# 21_GPIOs_EXP.net
KiCad netlist of a schematic drawn in Altium Designer
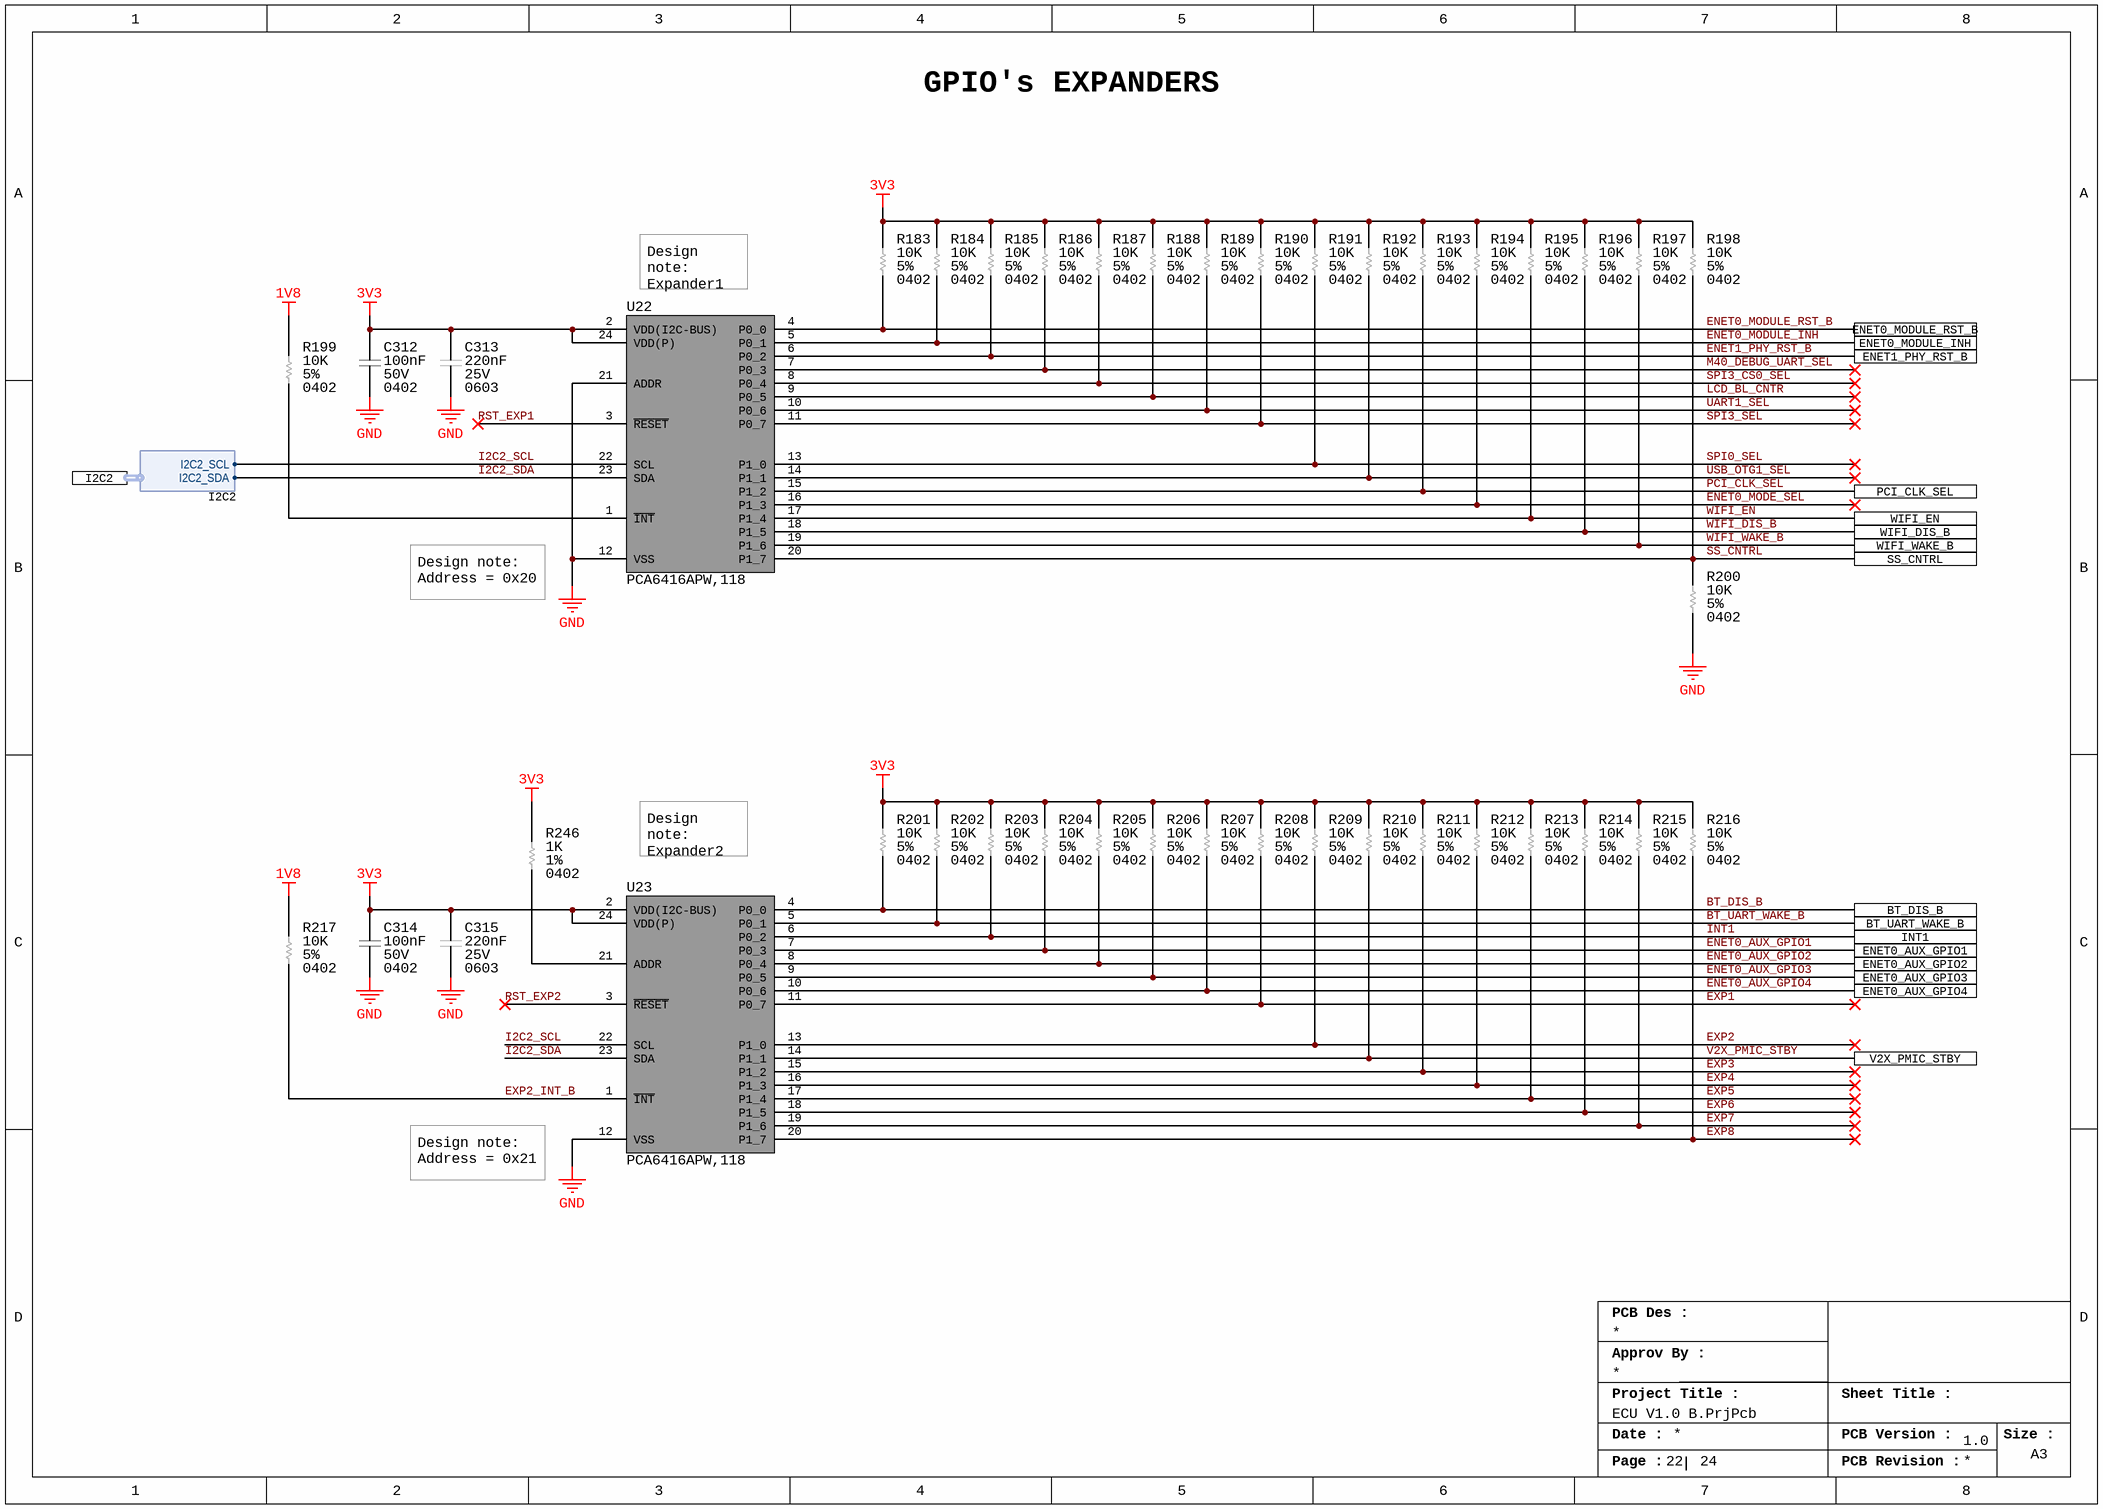
[diagram p0: 21_GPIOs_EXP.SchDoc]

(export (version "E")
  (design (tool "Eeschema 10.0.6"))
  (components
    (comp (ref "C312")
      (value "GRM155R71H104KE14D")
      (footprint "CAP_0402_CAPC1005X05N")
      (description "Multilayer Ceramic Capacitor, 0.1 uF, 16 V, ± 10%, X7R, 0402 [1005 Metric]")
      (fields
        (field (name "MANUFACTURER") "Murata")
        (field (name "TOLERANCE") "10%")
        (field (name "VOLTAGE RATING") "50V")
        (field (name "CAPACITANCE") "100nF")
        (field (name "CASE/PACKAGE") "0402")
      )
      (libsource (lib "Electronic Devices_LIB") (part "CAP_100NF_50V_X7R_0402"))
    )
    (comp (ref "C313")
      (value "GRM188R71E224KA88D")
      (footprint "CAP_0603_CAPC1608X08N")
      (description "Multilayer Ceramic Capacitor, 0.22 uF, 25 V, ± 10%, X7R, 0603 [1608 Metric]")
      (fields
        (field (name "MANUFACTURER") "Murata")
        (field (name "TOLERANCE") "10%")
        (field (name "CASE/PACKAGE") "0603")
        (field (name "VOLTAGE RATING") "25V")
        (field (name "CAPACITANCE") "220nF")
      )
      (libsource (lib "Electronic Devices_LIB") (part "CAP_0.22uF_25V_X7R_0603"))
    )
    (comp (ref "C314")
      (value "GRM155R71H104KE14D")
      (footprint "CAP_0402_CAPC1005X05N")
      (description "Multilayer Ceramic Capacitor, 0.1 uF, 16 V, ± 10%, X7R, 0402 [1005 Metric]")
      (fields
        (field (name "MANUFACTURER") "Murata")
        (field (name "TOLERANCE") "10%")
        (field (name "VOLTAGE RATING") "50V")
        (field (name "CAPACITANCE") "100nF")
        (field (name "CASE/PACKAGE") "0402")
      )
      (libsource (lib "Electronic Devices_LIB") (part "CAP_100NF_50V_X7R_0402"))
    )
    (comp (ref "C315")
      (value "GRM188R71E224KA88D")
      (footprint "CAP_0603_CAPC1608X08N")
      (description "Multilayer Ceramic Capacitor, 0.22 uF, 25 V, ± 10%, X7R, 0603 [1608 Metric]")
      (fields
        (field (name "MANUFACTURER") "Murata")
        (field (name "TOLERANCE") "10%")
        (field (name "CASE/PACKAGE") "0603")
        (field (name "VOLTAGE RATING") "25V")
        (field (name "CAPACITANCE") "220nF")
      )
      (libsource (lib "Electronic Devices_LIB") (part "CAP_0.22uF_25V_X7R_0603"))
    )
    (comp (ref "R183")
      (value "ERJ-2GEJ103X")
      (footprint "RES_0402_RESC1005X04N")
      (description "Res Thick Film 0402 10K Ohm 5% 1/10W ±200ppm/°C Molded SMD Punched Carrier T/R")
      (fields
        (field (name "MANUFACTURER") "Panasonic")
        (field (name "TOLERANCE") "5%")
        (field (name "RESISTANCE") "10K")
        (field (name "CASE/PACKAGE") "0402")
      )
      (libsource (lib "Electronic Devices_LIB") (part "RES_10K_5%_100mW_0402"))
    )
    (comp (ref "R184")
      (value "ERJ-2GEJ103X")
      (footprint "RES_0402_RESC1005X04N")
      (description "Res Thick Film 0402 10K Ohm 5% 1/10W ±200ppm/°C Molded SMD Punched Carrier T/R")
      (fields
        (field (name "MANUFACTURER") "Panasonic")
        (field (name "TOLERANCE") "5%")
        (field (name "RESISTANCE") "10K")
        (field (name "CASE/PACKAGE") "0402")
      )
      (libsource (lib "Electronic Devices_LIB") (part "RES_10K_5%_100mW_0402"))
    )
    (comp (ref "R185")
      (value "ERJ-2GEJ103X")
      (footprint "RES_0402_RESC1005X04N")
      (description "Res Thick Film 0402 10K Ohm 5% 1/10W ±200ppm/°C Molded SMD Punched Carrier T/R")
      (fields
        (field (name "MANUFACTURER") "Panasonic")
        (field (name "TOLERANCE") "5%")
        (field (name "RESISTANCE") "10K")
        (field (name "CASE/PACKAGE") "0402")
      )
      (libsource (lib "Electronic Devices_LIB") (part "RES_10K_5%_100mW_0402"))
    )
    (comp (ref "R186")
      (value "ERJ-2GEJ103X")
      (footprint "RES_0402_RESC1005X04N")
      (description "Res Thick Film 0402 10K Ohm 5% 1/10W ±200ppm/°C Molded SMD Punched Carrier T/R")
      (fields
        (field (name "MANUFACTURER") "Panasonic")
        (field (name "TOLERANCE") "5%")
        (field (name "RESISTANCE") "10K")
        (field (name "CASE/PACKAGE") "0402")
      )
      (libsource (lib "Electronic Devices_LIB") (part "RES_10K_5%_100mW_0402"))
    )
    (comp (ref "R187")
      (value "ERJ-2GEJ103X")
      (footprint "RES_0402_RESC1005X04N")
      (description "Res Thick Film 0402 10K Ohm 5% 1/10W ±200ppm/°C Molded SMD Punched Carrier T/R")
      (fields
        (field (name "MANUFACTURER") "Panasonic")
        (field (name "TOLERANCE") "5%")
        (field (name "RESISTANCE") "10K")
        (field (name "CASE/PACKAGE") "0402")
      )
      (libsource (lib "Electronic Devices_LIB") (part "RES_10K_5%_100mW_0402"))
    )
    (comp (ref "R188")
      (value "ERJ-2GEJ103X")
      (footprint "RES_0402_RESC1005X04N")
      (description "Res Thick Film 0402 10K Ohm 5% 1/10W ±200ppm/°C Molded SMD Punched Carrier T/R")
      (fields
        (field (name "MANUFACTURER") "Panasonic")
        (field (name "TOLERANCE") "5%")
        (field (name "RESISTANCE") "10K")
        (field (name "CASE/PACKAGE") "0402")
      )
      (libsource (lib "Electronic Devices_LIB") (part "RES_10K_5%_100mW_0402"))
    )
    (comp (ref "R189")
      (value "ERJ-2GEJ103X")
      (footprint "RES_0402_RESC1005X04N")
      (description "Res Thick Film 0402 10K Ohm 5% 1/10W ±200ppm/°C Molded SMD Punched Carrier T/R")
      (fields
        (field (name "MANUFACTURER") "Panasonic")
        (field (name "TOLERANCE") "5%")
        (field (name "RESISTANCE") "10K")
        (field (name "CASE/PACKAGE") "0402")
      )
      (libsource (lib "Electronic Devices_LIB") (part "RES_10K_5%_100mW_0402"))
    )
    (comp (ref "R190")
      (value "ERJ-2GEJ103X")
      (footprint "RES_0402_RESC1005X04N")
      (description "Res Thick Film 0402 10K Ohm 5% 1/10W ±200ppm/°C Molded SMD Punched Carrier T/R")
      (fields
        (field (name "MANUFACTURER") "Panasonic")
        (field (name "TOLERANCE") "5%")
        (field (name "RESISTANCE") "10K")
        (field (name "CASE/PACKAGE") "0402")
      )
      (libsource (lib "Electronic Devices_LIB") (part "RES_10K_5%_100mW_0402"))
    )
    (comp (ref "R191")
      (value "ERJ-2GEJ103X")
      (footprint "RES_0402_RESC1005X04N")
      (description "Res Thick Film 0402 10K Ohm 5% 1/10W ±200ppm/°C Molded SMD Punched Carrier T/R")
      (fields
        (field (name "MANUFACTURER") "Panasonic")
        (field (name "TOLERANCE") "5%")
        (field (name "RESISTANCE") "10K")
        (field (name "CASE/PACKAGE") "0402")
      )
      (libsource (lib "Electronic Devices_LIB") (part "RES_10K_5%_100mW_0402"))
    )
    (comp (ref "R192")
      (value "ERJ-2GEJ103X")
      (footprint "RES_0402_RESC1005X04N")
      (description "Res Thick Film 0402 10K Ohm 5% 1/10W ±200ppm/°C Molded SMD Punched Carrier T/R")
      (fields
        (field (name "MANUFACTURER") "Panasonic")
        (field (name "TOLERANCE") "5%")
        (field (name "RESISTANCE") "10K")
        (field (name "CASE/PACKAGE") "0402")
      )
      (libsource (lib "Electronic Devices_LIB") (part "RES_10K_5%_100mW_0402"))
    )
    (comp (ref "R193")
      (value "ERJ-2GEJ103X")
      (footprint "RES_0402_RESC1005X04N")
      (description "Res Thick Film 0402 10K Ohm 5% 1/10W ±200ppm/°C Molded SMD Punched Carrier T/R")
      (fields
        (field (name "MANUFACTURER") "Panasonic")
        (field (name "TOLERANCE") "5%")
        (field (name "RESISTANCE") "10K")
        (field (name "CASE/PACKAGE") "0402")
      )
      (libsource (lib "Electronic Devices_LIB") (part "RES_10K_5%_100mW_0402"))
    )
    (comp (ref "R194")
      (value "ERJ-2GEJ103X")
      (footprint "RES_0402_RESC1005X04N")
      (description "Res Thick Film 0402 10K Ohm 5% 1/10W ±200ppm/°C Molded SMD Punched Carrier T/R")
      (fields
        (field (name "MANUFACTURER") "Panasonic")
        (field (name "TOLERANCE") "5%")
        (field (name "RESISTANCE") "10K")
        (field (name "CASE/PACKAGE") "0402")
      )
      (libsource (lib "Electronic Devices_LIB") (part "RES_10K_5%_100mW_0402"))
    )
    (comp (ref "R195")
      (value "ERJ-2GEJ103X")
      (footprint "RES_0402_RESC1005X04N")
      (description "Res Thick Film 0402 10K Ohm 5% 1/10W ±200ppm/°C Molded SMD Punched Carrier T/R")
      (fields
        (field (name "MANUFACTURER") "Panasonic")
        (field (name "TOLERANCE") "5%")
        (field (name "RESISTANCE") "10K")
        (field (name "CASE/PACKAGE") "0402")
      )
      (libsource (lib "Electronic Devices_LIB") (part "RES_10K_5%_100mW_0402"))
    )
    (comp (ref "R196")
      (value "ERJ-2GEJ103X")
      (footprint "RES_0402_RESC1005X04N")
      (description "Res Thick Film 0402 10K Ohm 5% 1/10W ±200ppm/°C Molded SMD Punched Carrier T/R")
      (fields
        (field (name "MANUFACTURER") "Panasonic")
        (field (name "TOLERANCE") "5%")
        (field (name "RESISTANCE") "10K")
        (field (name "CASE/PACKAGE") "0402")
      )
      (libsource (lib "Electronic Devices_LIB") (part "RES_10K_5%_100mW_0402"))
    )
    (comp (ref "R197")
      (value "ERJ-2GEJ103X")
      (footprint "RES_0402_RESC1005X04N")
      (description "Res Thick Film 0402 10K Ohm 5% 1/10W ±200ppm/°C Molded SMD Punched Carrier T/R")
      (fields
        (field (name "MANUFACTURER") "Panasonic")
        (field (name "TOLERANCE") "5%")
        (field (name "RESISTANCE") "10K")
        (field (name "CASE/PACKAGE") "0402")
      )
      (libsource (lib "Electronic Devices_LIB") (part "RES_10K_5%_100mW_0402"))
    )
    (comp (ref "R198")
      (value "ERJ-2GEJ103X")
      (footprint "RES_0402_RESC1005X04N")
      (description "Res Thick Film 0402 10K Ohm 5% 1/10W ±200ppm/°C Molded SMD Punched Carrier T/R")
      (fields
        (field (name "MANUFACTURER") "Panasonic")
        (field (name "TOLERANCE") "5%")
        (field (name "RESISTANCE") "10K")
        (field (name "CASE/PACKAGE") "0402")
      )
      (libsource (lib "Electronic Devices_LIB") (part "RES_10K_5%_100mW_0402"))
    )
    (comp (ref "R199")
      (value "ERJ-2GEJ103X")
      (footprint "RES_0402_RESC1005X04N")
      (description "Res Thick Film 0402 10K Ohm 5% 1/10W ±200ppm/°C Molded SMD Punched Carrier T/R")
      (fields
        (field (name "MANUFACTURER") "Panasonic")
        (field (name "TOLERANCE") "5%")
        (field (name "RESISTANCE") "10K")
        (field (name "CASE/PACKAGE") "0402")
      )
      (libsource (lib "Electronic Devices_LIB") (part "RES_10K_5%_100mW_0402"))
    )
    (comp (ref "R200")
      (value "ERJ-2GEJ103X")
      (footprint "RES_0402_RESC1005X04N")
      (description "Res Thick Film 0402 10K Ohm 5% 1/10W ±200ppm/°C Molded SMD Punched Carrier T/R")
      (fields
        (field (name "MANUFACTURER") "Panasonic")
        (field (name "TOLERANCE") "5%")
        (field (name "RESISTANCE") "10K")
        (field (name "CASE/PACKAGE") "0402")
      )
      (libsource (lib "Electronic Devices_LIB") (part "RES_10K_5%_100mW_0402"))
    )
    (comp (ref "R201")
      (value "ERJ-2GEJ103X")
      (footprint "RES_0402_RESC1005X04N")
      (description "Res Thick Film 0402 10K Ohm 5% 1/10W ±200ppm/°C Molded SMD Punched Carrier T/R")
      (fields
        (field (name "MANUFACTURER") "Panasonic")
        (field (name "TOLERANCE") "5%")
        (field (name "RESISTANCE") "10K")
        (field (name "CASE/PACKAGE") "0402")
      )
      (libsource (lib "Electronic Devices_LIB") (part "RES_10K_5%_100mW_0402"))
    )
    (comp (ref "R202")
      (value "ERJ-2GEJ103X")
      (footprint "RES_0402_RESC1005X04N")
      (description "Res Thick Film 0402 10K Ohm 5% 1/10W ±200ppm/°C Molded SMD Punched Carrier T/R")
      (fields
        (field (name "MANUFACTURER") "Panasonic")
        (field (name "TOLERANCE") "5%")
        (field (name "RESISTANCE") "10K")
        (field (name "CASE/PACKAGE") "0402")
      )
      (libsource (lib "Electronic Devices_LIB") (part "RES_10K_5%_100mW_0402"))
    )
    (comp (ref "R203")
      (value "ERJ-2GEJ103X")
      (footprint "RES_0402_RESC1005X04N")
      (description "Res Thick Film 0402 10K Ohm 5% 1/10W ±200ppm/°C Molded SMD Punched Carrier T/R")
      (fields
        (field (name "MANUFACTURER") "Panasonic")
        (field (name "TOLERANCE") "5%")
        (field (name "RESISTANCE") "10K")
        (field (name "CASE/PACKAGE") "0402")
      )
      (libsource (lib "Electronic Devices_LIB") (part "RES_10K_5%_100mW_0402"))
    )
    (comp (ref "R204")
      (value "ERJ-2GEJ103X")
      (footprint "RES_0402_RESC1005X04N")
      (description "Res Thick Film 0402 10K Ohm 5% 1/10W ±200ppm/°C Molded SMD Punched Carrier T/R")
      (fields
        (field (name "MANUFACTURER") "Panasonic")
        (field (name "TOLERANCE") "5%")
        (field (name "RESISTANCE") "10K")
        (field (name "CASE/PACKAGE") "0402")
      )
      (libsource (lib "Electronic Devices_LIB") (part "RES_10K_5%_100mW_0402"))
    )
    (comp (ref "R205")
      (value "ERJ-2GEJ103X")
      (footprint "RES_0402_RESC1005X04N")
      (description "Res Thick Film 0402 10K Ohm 5% 1/10W ±200ppm/°C Molded SMD Punched Carrier T/R")
      (fields
        (field (name "MANUFACTURER") "Panasonic")
        (field (name "TOLERANCE") "5%")
        (field (name "RESISTANCE") "10K")
        (field (name "CASE/PACKAGE") "0402")
      )
      (libsource (lib "Electronic Devices_LIB") (part "RES_10K_5%_100mW_0402"))
    )
    (comp (ref "R206")
      (value "ERJ-2GEJ103X")
      (footprint "RES_0402_RESC1005X04N")
      (description "Res Thick Film 0402 10K Ohm 5% 1/10W ±200ppm/°C Molded SMD Punched Carrier T/R")
      (fields
        (field (name "MANUFACTURER") "Panasonic")
        (field (name "TOLERANCE") "5%")
        (field (name "RESISTANCE") "10K")
        (field (name "CASE/PACKAGE") "0402")
      )
      (libsource (lib "Electronic Devices_LIB") (part "RES_10K_5%_100mW_0402"))
    )
    (comp (ref "R207")
      (value "ERJ-2GEJ103X")
      (footprint "RES_0402_RESC1005X04N")
      (description "Res Thick Film 0402 10K Ohm 5% 1/10W ±200ppm/°C Molded SMD Punched Carrier T/R")
      (fields
        (field (name "MANUFACTURER") "Panasonic")
        (field (name "TOLERANCE") "5%")
        (field (name "RESISTANCE") "10K")
        (field (name "CASE/PACKAGE") "0402")
      )
      (libsource (lib "Electronic Devices_LIB") (part "RES_10K_5%_100mW_0402"))
    )
    (comp (ref "R208")
      (value "ERJ-2GEJ103X")
      (footprint "RES_0402_RESC1005X04N")
      (description "Res Thick Film 0402 10K Ohm 5% 1/10W ±200ppm/°C Molded SMD Punched Carrier T/R")
      (fields
        (field (name "MANUFACTURER") "Panasonic")
        (field (name "TOLERANCE") "5%")
        (field (name "RESISTANCE") "10K")
        (field (name "CASE/PACKAGE") "0402")
      )
      (libsource (lib "Electronic Devices_LIB") (part "RES_10K_5%_100mW_0402"))
    )
    (comp (ref "R209")
      (value "ERJ-2GEJ103X")
      (footprint "RES_0402_RESC1005X04N")
      (description "Res Thick Film 0402 10K Ohm 5% 1/10W ±200ppm/°C Molded SMD Punched Carrier T/R")
      (fields
        (field (name "MANUFACTURER") "Panasonic")
        (field (name "TOLERANCE") "5%")
        (field (name "RESISTANCE") "10K")
        (field (name "CASE/PACKAGE") "0402")
      )
      (libsource (lib "Electronic Devices_LIB") (part "RES_10K_5%_100mW_0402"))
    )
    (comp (ref "R210")
      (value "ERJ-2GEJ103X")
      (footprint "RES_0402_RESC1005X04N")
      (description "Res Thick Film 0402 10K Ohm 5% 1/10W ±200ppm/°C Molded SMD Punched Carrier T/R")
      (fields
        (field (name "MANUFACTURER") "Panasonic")
        (field (name "TOLERANCE") "5%")
        (field (name "RESISTANCE") "10K")
        (field (name "CASE/PACKAGE") "0402")
      )
      (libsource (lib "Electronic Devices_LIB") (part "RES_10K_5%_100mW_0402"))
    )
    (comp (ref "R211")
      (value "ERJ-2GEJ103X")
      (footprint "RES_0402_RESC1005X04N")
      (description "Res Thick Film 0402 10K Ohm 5% 1/10W ±200ppm/°C Molded SMD Punched Carrier T/R")
      (fields
        (field (name "MANUFACTURER") "Panasonic")
        (field (name "TOLERANCE") "5%")
        (field (name "RESISTANCE") "10K")
        (field (name "CASE/PACKAGE") "0402")
      )
      (libsource (lib "Electronic Devices_LIB") (part "RES_10K_5%_100mW_0402"))
    )
    (comp (ref "R212")
      (value "ERJ-2GEJ103X")
      (footprint "RES_0402_RESC1005X04N")
      (description "Res Thick Film 0402 10K Ohm 5% 1/10W ±200ppm/°C Molded SMD Punched Carrier T/R")
      (fields
        (field (name "MANUFACTURER") "Panasonic")
        (field (name "TOLERANCE") "5%")
        (field (name "RESISTANCE") "10K")
        (field (name "CASE/PACKAGE") "0402")
      )
      (libsource (lib "Electronic Devices_LIB") (part "RES_10K_5%_100mW_0402"))
    )
    (comp (ref "R213")
      (value "ERJ-2GEJ103X")
      (footprint "RES_0402_RESC1005X04N")
      (description "Res Thick Film 0402 10K Ohm 5% 1/10W ±200ppm/°C Molded SMD Punched Carrier T/R")
      (fields
        (field (name "MANUFACTURER") "Panasonic")
        (field (name "TOLERANCE") "5%")
        (field (name "RESISTANCE") "10K")
        (field (name "CASE/PACKAGE") "0402")
      )
      (libsource (lib "Electronic Devices_LIB") (part "RES_10K_5%_100mW_0402"))
    )
    (comp (ref "R214")
      (value "ERJ-2GEJ103X")
      (footprint "RES_0402_RESC1005X04N")
      (description "Res Thick Film 0402 10K Ohm 5% 1/10W ±200ppm/°C Molded SMD Punched Carrier T/R")
      (fields
        (field (name "MANUFACTURER") "Panasonic")
        (field (name "TOLERANCE") "5%")
        (field (name "RESISTANCE") "10K")
        (field (name "CASE/PACKAGE") "0402")
      )
      (libsource (lib "Electronic Devices_LIB") (part "RES_10K_5%_100mW_0402"))
    )
    (comp (ref "R215")
      (value "ERJ-2GEJ103X")
      (footprint "RES_0402_RESC1005X04N")
      (description "Res Thick Film 0402 10K Ohm 5% 1/10W ±200ppm/°C Molded SMD Punched Carrier T/R")
      (fields
        (field (name "MANUFACTURER") "Panasonic")
        (field (name "TOLERANCE") "5%")
        (field (name "RESISTANCE") "10K")
        (field (name "CASE/PACKAGE") "0402")
      )
      (libsource (lib "Electronic Devices_LIB") (part "RES_10K_5%_100mW_0402"))
    )
    (comp (ref "R216")
      (value "ERJ-2GEJ103X")
      (footprint "RES_0402_RESC1005X04N")
      (description "Res Thick Film 0402 10K Ohm 5% 1/10W ±200ppm/°C Molded SMD Punched Carrier T/R")
      (fields
        (field (name "MANUFACTURER") "Panasonic")
        (field (name "TOLERANCE") "5%")
        (field (name "RESISTANCE") "10K")
        (field (name "CASE/PACKAGE") "0402")
      )
      (libsource (lib "Electronic Devices_LIB") (part "RES_10K_5%_100mW_0402"))
    )
    (comp (ref "R217")
      (value "ERJ-2GEJ103X")
      (footprint "RES_0402_RESC1005X04N")
      (description "Res Thick Film 0402 10K Ohm 5% 1/10W ±200ppm/°C Molded SMD Punched Carrier T/R")
      (fields
        (field (name "MANUFACTURER") "Panasonic")
        (field (name "TOLERANCE") "5%")
        (field (name "RESISTANCE") "10K")
        (field (name "CASE/PACKAGE") "0402")
      )
      (libsource (lib "Electronic Devices_LIB") (part "RES_10K_5%_100mW_0402"))
    )
    (comp (ref "R246")
      (value "ERJ-2RKF1001X")
      (footprint "RES_0402_RESC1005X04N")
      (description "RES SMD 1K OHM 1% 1/10W 0402")
      (fields
        (field (name "MANUFACTURER") "Panasonic")
        (field (name "RESISTANCE") "1K")
        (field (name "TOLERANCE") "1%")
        (field (name "CASE/PACKAGE") "0402")
      )
      (libsource (lib "Electronic Devices_LIB") (part "RES_1K_1%_100mW_0402"))
    )
    (comp (ref "U22")
      (value "PCA6416APW,118")
      (footprint "PCA6416APW118")
      (description "I2C/SMBus Interface 100kHz/400kHz 5.5V 24-Pin TSSOP T/R")
      (fields (field (name "MANUFACTURER") "NXP Semiconductors"))
      (libsource (lib "Electronic Devices_LIB") (part "IC_EXPANDER_16_PCA6416APW,118"))
    )
    (comp (ref "U23")
      (value "PCA6416APW,118")
      (footprint "PCA6416APW118")
      (description "I2C/SMBus Interface 100kHz/400kHz 5.5V 24-Pin TSSOP T/R")
      (fields (field (name "MANUFACTURER") "NXP Semiconductors"))
      (libsource (lib "Electronic Devices_LIB") (part "IC_EXPANDER_16_PCA6416APW,118"))
    )
  )
  (nets
    (net (code "2") (name "/BT_DIS_B") (class "Default")
      (node (ref "R201") (pin "1") (pinfunction "1_1") (pintype "passive"))
      (node (ref "U23") (pin "4") (pinfunction "P0_0_4") (pintype "passive"))
    )
    (net (code "3") (name "/BT_UART_WAKE_B") (class "Default")
      (node (ref "R202") (pin "1") (pinfunction "1_1") (pintype "passive"))
      (node (ref "U23") (pin "5") (pinfunction "P0_1_5") (pintype "passive"))
    )
    (net (code "4") (name "/ENET0_AUX_GPIO1") (class "Default")
      (node (ref "R204") (pin "1") (pinfunction "1_1") (pintype "passive"))
      (node (ref "U23") (pin "7") (pinfunction "P0_3_7") (pintype "passive"))
    )
    (net (code "5") (name "/ENET0_AUX_GPIO2") (class "Default")
      (node (ref "R205") (pin "1") (pinfunction "1_1") (pintype "passive"))
      (node (ref "U23") (pin "8") (pinfunction "P0_4_8") (pintype "passive"))
    )
    (net (code "6") (name "/ENET0_AUX_GPIO3") (class "Default")
      (node (ref "R206") (pin "1") (pinfunction "1_1") (pintype "passive"))
      (node (ref "U23") (pin "9") (pinfunction "P0_5_9") (pintype "passive"))
    )
    (net (code "7") (name "/ENET0_AUX_GPIO4") (class "Default")
      (node (ref "R207") (pin "1") (pinfunction "1_1") (pintype "passive"))
      (node (ref "U23") (pin "10") (pinfunction "P0_6_10") (pintype "passive"))
    )
    (net (code "8") (name "/ENET0_MODE_SEL") (class "Default")
      (node (ref "R194") (pin "1") (pinfunction "1_1") (pintype "passive"))
      (node (ref "U22") (pin "16") (pinfunction "P1_3_16") (pintype "passive"))
    )
    (net (code "9") (name "/ENET0_MODULE_INH") (class "Default")
      (node (ref "R184") (pin "1") (pinfunction "1_1") (pintype "passive"))
      (node (ref "U22") (pin "5") (pinfunction "P0_1_5") (pintype "passive"))
    )
    (net (code "10") (name "/ENET0_MODULE_RST_B") (class "Default")
      (node (ref "R183") (pin "1") (pinfunction "1_1") (pintype "passive"))
      (node (ref "U22") (pin "4") (pinfunction "P0_0_4") (pintype "passive"))
    )
    (net (code "11") (name "/ENET1_PHY_RST_B") (class "Default")
      (node (ref "R185") (pin "1") (pinfunction "1_1") (pintype "passive"))
      (node (ref "U22") (pin "6") (pinfunction "P0_2_6") (pintype "passive"))
    )
    (net (code "12") (name "/EXP1") (class "Default")
      (node (ref "R208") (pin "1") (pinfunction "1_1") (pintype "passive"))
      (node (ref "U23") (pin "11") (pinfunction "P0_7_11") (pintype "passive"))
    )
    (net (code "13") (name "/EXP2") (class "Default")
      (node (ref "R209") (pin "1") (pinfunction "1_1") (pintype "passive"))
      (node (ref "U23") (pin "13") (pinfunction "P1_0_13") (pintype "passive"))
    )
    (net (code "14") (name "/EXP2_INT_B") (class "Default")
      (node (ref "R217") (pin "1") (pinfunction "1_1") (pintype "passive"))
      (node (ref "U23") (pin "1") (pinfunction "~{INT}_1") (pintype "passive"))
    )
    (net (code "15") (name "/EXP3") (class "Default")
      (node (ref "R211") (pin "1") (pinfunction "1_1") (pintype "passive"))
      (node (ref "U23") (pin "15") (pinfunction "P1_2_15") (pintype "passive"))
    )
    (net (code "16") (name "/EXP4") (class "Default")
      (node (ref "R212") (pin "1") (pinfunction "1_1") (pintype "passive"))
      (node (ref "U23") (pin "16") (pinfunction "P1_3_16") (pintype "passive"))
    )
    (net (code "17") (name "/EXP5") (class "Default")
      (node (ref "R213") (pin "1") (pinfunction "1_1") (pintype "passive"))
      (node (ref "U23") (pin "17") (pinfunction "P1_4_17") (pintype "passive"))
    )
    (net (code "18") (name "/EXP6") (class "Default")
      (node (ref "R214") (pin "1") (pinfunction "1_1") (pintype "passive"))
      (node (ref "U23") (pin "18") (pinfunction "P1_5_18") (pintype "passive"))
    )
    (net (code "19") (name "/EXP7") (class "Default")
      (node (ref "R215") (pin "1") (pinfunction "1_1") (pintype "passive"))
      (node (ref "U23") (pin "19") (pinfunction "P1_6_19") (pintype "passive"))
    )
    (net (code "20") (name "/EXP8") (class "Default")
      (node (ref "R216") (pin "1") (pinfunction "1_1") (pintype "passive"))
      (node (ref "U23") (pin "20") (pinfunction "P1_7_20") (pintype "passive"))
    )
    (net (code "21") (name "/I2C2_SCL") (class "Default")
      (node (ref "U22") (pin "22") (pinfunction "SCL_22") (pintype "passive"))
      (node (ref "U23") (pin "22") (pinfunction "SCL_22") (pintype "passive"))
    )
    (net (code "22") (name "/I2C2_SDA") (class "Default")
      (node (ref "U22") (pin "23") (pinfunction "SDA_23") (pintype "passive"))
      (node (ref "U23") (pin "23") (pinfunction "SDA_23") (pintype "passive"))
    )
    (net (code "23") (name "/INT1") (class "Default")
      (node (ref "R203") (pin "1") (pinfunction "1_1") (pintype "passive"))
      (node (ref "U23") (pin "6") (pinfunction "P0_2_6") (pintype "passive"))
    )
    (net (code "24") (name "/LCD_BL_CNTR") (class "Default")
      (node (ref "R188") (pin "1") (pinfunction "1_1") (pintype "passive"))
      (node (ref "U22") (pin "9") (pinfunction "P0_5_9") (pintype "passive"))
    )
    (net (code "25") (name "/M40_DEBUG_UART_SEL") (class "Default")
      (node (ref "R186") (pin "1") (pinfunction "1_1") (pintype "passive"))
      (node (ref "U22") (pin "7") (pinfunction "P0_3_7") (pintype "passive"))
    )
    (net (code "26") (name "/PCI_CLK_SEL") (class "Default")
      (node (ref "R193") (pin "1") (pinfunction "1_1") (pintype "passive"))
      (node (ref "U22") (pin "15") (pinfunction "P1_2_15") (pintype "passive"))
    )
    (net (code "27") (name "/RST_EXP1") (class "Default")
      (node (ref "U22") (pin "3") (pinfunction "~{RESET}_3") (pintype "passive+no_connect"))
    )
    (net (code "28") (name "/RST_EXP2") (class "Default")
      (node (ref "U23") (pin "3") (pinfunction "~{RESET}_3") (pintype "passive+no_connect"))
    )
    (net (code "29") (name "/SPI0_SEL") (class "Default")
      (node (ref "R191") (pin "1") (pinfunction "1_1") (pintype "passive"))
      (node (ref "U22") (pin "13") (pinfunction "P1_0_13") (pintype "passive"))
    )
    (net (code "30") (name "/SPI3_CS0_SEL") (class "Default")
      (node (ref "R187") (pin "1") (pinfunction "1_1") (pintype "passive"))
      (node (ref "U22") (pin "8") (pinfunction "P0_4_8") (pintype "passive"))
    )
    (net (code "31") (name "/SPI3_SEL") (class "Default")
      (node (ref "R190") (pin "1") (pinfunction "1_1") (pintype "passive"))
      (node (ref "U22") (pin "11") (pinfunction "P0_7_11") (pintype "passive"))
    )
    (net (code "32") (name "/SS_CNTRL") (class "Default")
      (node (ref "R198") (pin "1") (pinfunction "1_1") (pintype "passive"))
      (node (ref "R200") (pin "2") (pinfunction "2_2") (pintype "passive"))
      (node (ref "U22") (pin "20") (pinfunction "P1_7_20") (pintype "passive"))
    )
    (net (code "33") (name "/UART1_SEL") (class "Default")
      (node (ref "R189") (pin "1") (pinfunction "1_1") (pintype "passive"))
      (node (ref "U22") (pin "10") (pinfunction "P0_6_10") (pintype "passive"))
    )
    (net (code "34") (name "/USB_OTG1_SEL") (class "Default")
      (node (ref "R192") (pin "1") (pinfunction "1_1") (pintype "passive"))
      (node (ref "U22") (pin "14") (pinfunction "P1_1_14") (pintype "passive"))
    )
    (net (code "35") (name "/V2X_PMIC_STBY") (class "Default")
      (node (ref "R210") (pin "1") (pinfunction "1_1") (pintype "passive"))
      (node (ref "U23") (pin "14") (pinfunction "P1_1_14") (pintype "passive"))
    )
    (net (code "36") (name "/WIFI_DIS_B") (class "Default")
      (node (ref "R196") (pin "1") (pinfunction "1_1") (pintype "passive"))
      (node (ref "U22") (pin "18") (pinfunction "P1_5_18") (pintype "passive"))
    )
    (net (code "37") (name "/WIFI_EN") (class "Default")
      (node (ref "R195") (pin "1") (pinfunction "1_1") (pintype "passive"))
      (node (ref "U22") (pin "17") (pinfunction "P1_4_17") (pintype "passive"))
    )
    (net (code "38") (name "/WIFI_WAKE_B") (class "Default")
      (node (ref "R197") (pin "1") (pinfunction "1_1") (pintype "passive"))
      (node (ref "U22") (pin "19") (pinfunction "P1_6_19") (pintype "passive"))
    )
    (net (code "40") (name "1V8") (class "Default")
      (node (ref "R199") (pin "2") (pinfunction "2_2") (pintype "passive"))
      (node (ref "R217") (pin "2") (pinfunction "2_2") (pintype "passive"))
    )
    (net (code "41") (name "3V3") (class "Default")
      (node (ref "C312") (pin "2") (pinfunction "2_2") (pintype "passive"))
      (node (ref "C313") (pin "2") (pinfunction "2_2") (pintype "passive"))
      (node (ref "C314") (pin "2") (pinfunction "2_2") (pintype "passive"))
      (node (ref "C315") (pin "2") (pinfunction "2_2") (pintype "passive"))
      (node (ref "R183") (pin "2") (pinfunction "2_2") (pintype "passive"))
      (node (ref "R184") (pin "2") (pinfunction "2_2") (pintype "passive"))
      (node (ref "R185") (pin "2") (pinfunction "2_2") (pintype "passive"))
      (node (ref "R186") (pin "2") (pinfunction "2_2") (pintype "passive"))
      (node (ref "R187") (pin "2") (pinfunction "2_2") (pintype "passive"))
      (node (ref "R188") (pin "2") (pinfunction "2_2") (pintype "passive"))
      (node (ref "R189") (pin "2") (pinfunction "2_2") (pintype "passive"))
      (node (ref "R190") (pin "2") (pinfunction "2_2") (pintype "passive"))
      (node (ref "R191") (pin "2") (pinfunction "2_2") (pintype "passive"))
      (node (ref "R192") (pin "2") (pinfunction "2_2") (pintype "passive"))
      (node (ref "R193") (pin "2") (pinfunction "2_2") (pintype "passive"))
      (node (ref "R194") (pin "2") (pinfunction "2_2") (pintype "passive"))
      (node (ref "R195") (pin "2") (pinfunction "2_2") (pintype "passive"))
      (node (ref "R196") (pin "2") (pinfunction "2_2") (pintype "passive"))
      (node (ref "R197") (pin "2") (pinfunction "2_2") (pintype "passive"))
      (node (ref "R198") (pin "2") (pinfunction "2_2") (pintype "passive"))
      (node (ref "R201") (pin "2") (pinfunction "2_2") (pintype "passive"))
      (node (ref "R202") (pin "2") (pinfunction "2_2") (pintype "passive"))
      (node (ref "R203") (pin "2") (pinfunction "2_2") (pintype "passive"))
      (node (ref "R204") (pin "2") (pinfunction "2_2") (pintype "passive"))
      (node (ref "R205") (pin "2") (pinfunction "2_2") (pintype "passive"))
      (node (ref "R206") (pin "2") (pinfunction "2_2") (pintype "passive"))
      (node (ref "R207") (pin "2") (pinfunction "2_2") (pintype "passive"))
      (node (ref "R208") (pin "2") (pinfunction "2_2") (pintype "passive"))
      (node (ref "R209") (pin "2") (pinfunction "2_2") (pintype "passive"))
      (node (ref "R210") (pin "2") (pinfunction "2_2") (pintype "passive"))
      (node (ref "R211") (pin "2") (pinfunction "2_2") (pintype "passive"))
      (node (ref "R212") (pin "2") (pinfunction "2_2") (pintype "passive"))
      (node (ref "R213") (pin "2") (pinfunction "2_2") (pintype "passive"))
      (node (ref "R214") (pin "2") (pinfunction "2_2") (pintype "passive"))
      (node (ref "R215") (pin "2") (pinfunction "2_2") (pintype "passive"))
      (node (ref "R216") (pin "2") (pinfunction "2_2") (pintype "passive"))
      (node (ref "R246") (pin "2") (pinfunction "2_2") (pintype "passive"))
      (node (ref "U22") (pin "2") (pinfunction "VDD(I2C-BUS)_2") (pintype "passive"))
      (node (ref "U22") (pin "24") (pinfunction "VDD(P)_24") (pintype "passive"))
      (node (ref "U23") (pin "2") (pinfunction "VDD(I2C-BUS)_2") (pintype "passive"))
      (node (ref "U23") (pin "24") (pinfunction "VDD(P)_24") (pintype "passive"))
    )
    (net (code "42") (name "GND") (class "Default")
      (node (ref "C312") (pin "1") (pinfunction "1_1") (pintype "passive"))
      (node (ref "C313") (pin "1") (pinfunction "1_1") (pintype "passive"))
      (node (ref "C314") (pin "1") (pinfunction "1_1") (pintype "passive"))
      (node (ref "C315") (pin "1") (pinfunction "1_1") (pintype "passive"))
      (node (ref "R200") (pin "1") (pinfunction "1_1") (pintype "passive"))
      (node (ref "U22") (pin "12") (pinfunction "VSS_12") (pintype "passive"))
      (node (ref "U22") (pin "21") (pinfunction "ADDR_21") (pintype "passive"))
      (node (ref "U23") (pin "12") (pinfunction "VSS_12") (pintype "passive"))
    )
    (net (code "43") (name "Net-(U22-~{INT})") (class "Default")
      (node (ref "R199") (pin "1") (pinfunction "1_1") (pintype "passive"))
      (node (ref "U22") (pin "1") (pinfunction "~{INT}_1") (pintype "passive"))
    )
    (net (code "44") (name "Net-(U23-ADDR)") (class "Default")
      (node (ref "R246") (pin "1") (pinfunction "1_1") (pintype "passive"))
      (node (ref "U23") (pin "21") (pinfunction "ADDR_21") (pintype "passive"))
    )
  )
)
